# SensWear_Debug_DEBUG.net
KiCad netlist of a schematic drawn in Altium Designer
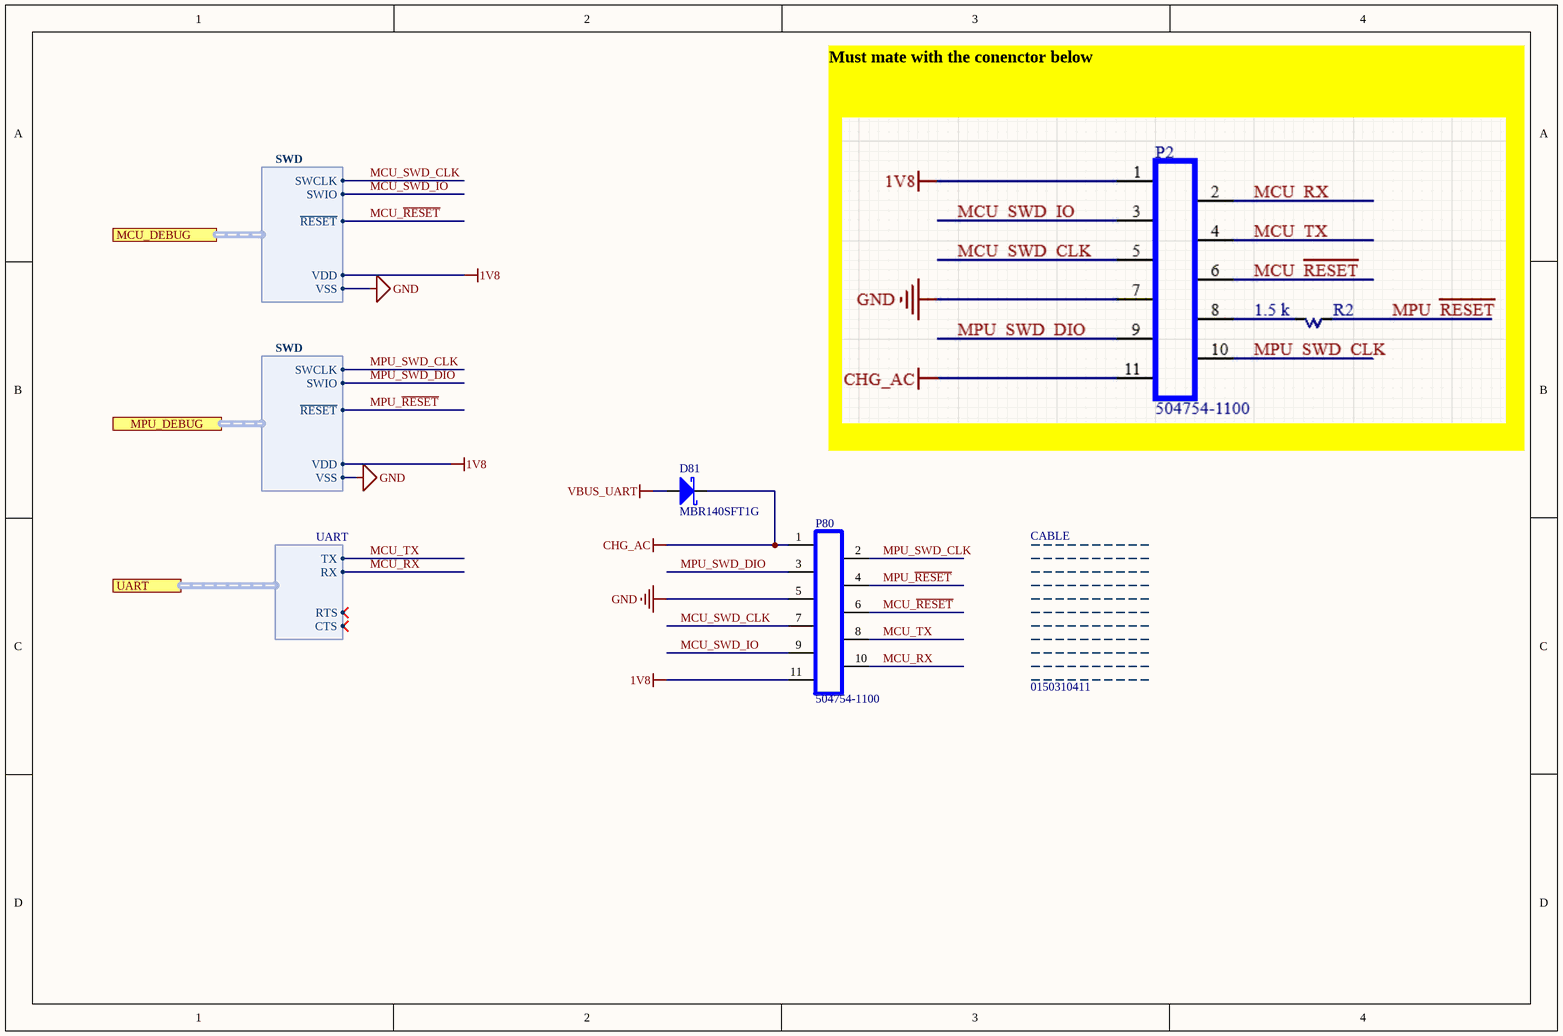
[diagram p0: SensWear_Debug_DEBUG.SchDoc]

(export (version "E")
  (design (tool "Eeschema 10.0.6"))
  (components
    (comp (ref "CABLE")
      (value "0150310411")
      (fields (field (name "MANUFACTURER") "Molex"))
      (libsource (lib "SensWearComponents") (part "0150310411"))
    )
    (comp (ref "D81")
      (value "MBR140SFT1G")
      (footprint "SODFL360X110-2N")
      (description "DIODE SCHOTTKY 40V 1A SOD123L")
      (fields (field (name "MANUFACTURER") "ON Semiconductor"))
      (libsource (lib "SensWearComponents") (part "MBR140SFT1G"))
    )
    (comp (ref "P80")
      (value "504754-1100")
      (footprint "5047541100__3")
      (description "Conn FFC/FPC Connector SKT 11 POS 0.3mm Solder RA SMD Easy-On™ T/R")
      (fields (field (name "MANUFACTURER") "Molex") (field (name "CHECKED") "FALSE"))
      (libsource (lib "SensWearComponents") (part "504754-1100__2"))
    )
  )
  (nets
    (net (code "3") (name "/MCU_RX") (class "Default")
      (node (ref "P80") (pin "10") (pinfunction "10_10") (pintype "passive"))
    )
    (net (code "4") (name "/MCU_SWD_CLK") (class "Default")
      (node (ref "P80") (pin "7") (pinfunction "7_7") (pintype "passive"))
    )
    (net (code "5") (name "/MCU_SWD_IO") (class "Default")
      (node (ref "P80") (pin "9") (pinfunction "9_9") (pintype "passive"))
    )
    (net (code "6") (name "/MCU_TX") (class "Default")
      (node (ref "P80") (pin "8") (pinfunction "8_8") (pintype "passive"))
    )
    (net (code "7") (name "/MCU_~{RESET}") (class "Default")
      (node (ref "P80") (pin "6") (pinfunction "6_6") (pintype "passive"))
    )
    (net (code "8") (name "/MPU_SWD_CLK") (class "Default")
      (node (ref "P80") (pin "2") (pinfunction "2_2") (pintype "passive"))
    )
    (net (code "9") (name "/MPU_SWD_DIO") (class "Default")
      (node (ref "P80") (pin "3") (pinfunction "3_3") (pintype "passive"))
    )
    (net (code "10") (name "/MPU_~{RESET}") (class "Default")
      (node (ref "P80") (pin "4") (pinfunction "4_4") (pintype "passive"))
    )
    (net (code "13") (name "1V8") (class "Default")
      (node (ref "P80") (pin "11") (pinfunction "11_11") (pintype "passive"))
    )
    (net (code "14") (name "CHG_AC") (class "Default")
      (node (ref "D81") (pin "1") (pinfunction "cathode_1") (pintype "passive"))
      (node (ref "P80") (pin "1") (pinfunction "1_1") (pintype "passive"))
    )
    (net (code "15") (name "GND") (class "Default")
      (node (ref "P80") (pin "5") (pinfunction "5_5") (pintype "passive"))
    )
    (net (code "16") (name "VBUS_UART") (class "Default")
      (node (ref "D81") (pin "2") (pinfunction "ANODE_2") (pintype "passive"))
    )
  )
)
